# KoncovaCast.net
KiCad netlist of a schematic drawn in EAGLE
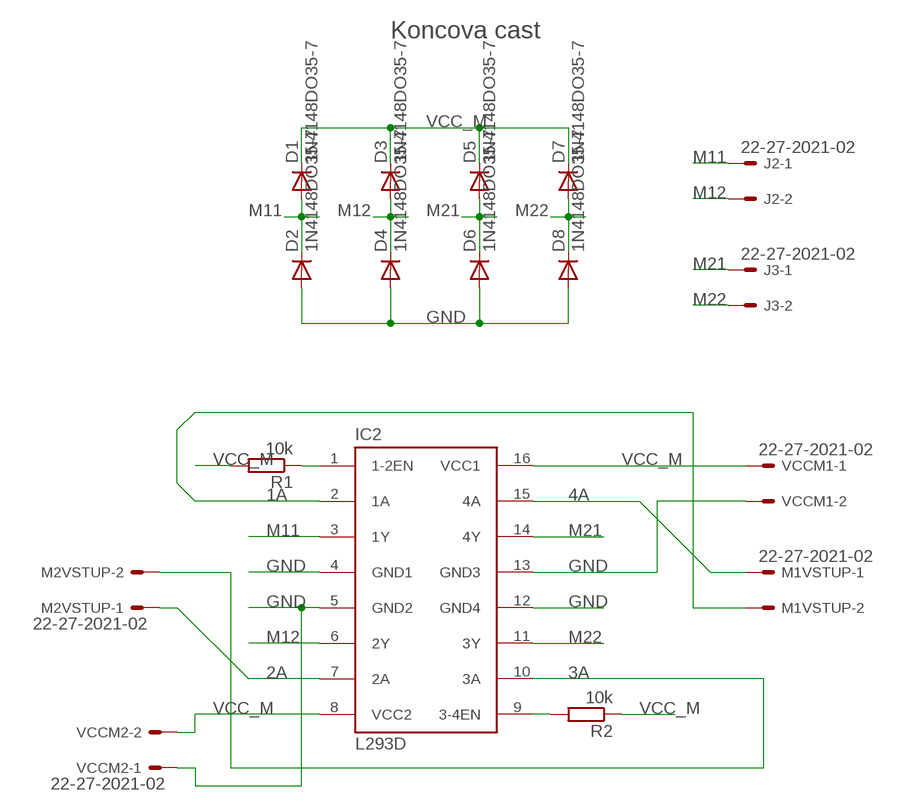
[diagram p0: schematic, sheet 1]

(export (version "E")
  (design (tool "Eeschema 10.0.6"))
  (components
    (comp (ref "D1")
      (value "1N4148DO35-7")
      (footprint "eagle-import:DO35-7")
      (libsource (lib "eagle-import") (part "1N4148DO35-7"))
    )
    (comp (ref "D2")
      (value "1N4148DO35-7")
      (footprint "eagle-import:DO35-7")
      (libsource (lib "eagle-import") (part "1N4148DO35-7"))
    )
    (comp (ref "D3")
      (value "1N4148DO35-7")
      (footprint "eagle-import:DO35-7")
      (libsource (lib "eagle-import") (part "1N4148DO35-7"))
    )
    (comp (ref "D4")
      (value "1N4148DO35-7")
      (footprint "eagle-import:DO35-7")
      (libsource (lib "eagle-import") (part "1N4148DO35-7"))
    )
    (comp (ref "D5")
      (value "1N4148DO35-7")
      (footprint "eagle-import:DO35-7")
      (libsource (lib "eagle-import") (part "1N4148DO35-7"))
    )
    (comp (ref "D6")
      (value "1N4148DO35-7")
      (footprint "eagle-import:DO35-7")
      (libsource (lib "eagle-import") (part "1N4148DO35-7"))
    )
    (comp (ref "D7")
      (value "1N4148DO35-7")
      (footprint "eagle-import:DO35-7")
      (libsource (lib "eagle-import") (part "1N4148DO35-7"))
    )
    (comp (ref "D8")
      (value "1N4148DO35-7")
      (footprint "eagle-import:DO35-7")
      (libsource (lib "eagle-import") (part "1N4148DO35-7"))
    )
    (comp (ref "IC2")
      (value "L293D")
      (footprint "eagle-import:DIL16")
      (libsource (lib "eagle-import") (part "L293D"))
    )
    (comp (ref "J2")
      (value "22-27-2021-02")
      (footprint "eagle-import:6410-02")
      (libsource (lib "eagle-import") (part "22-?-0227-2021"))
    )
    (comp (ref "J3")
      (value "22-27-2021-02")
      (footprint "eagle-import:6410-02")
      (libsource (lib "eagle-import") (part "22-?-0227-2021"))
    )
    (comp (ref "M1VSTUP")
      (value "22-27-2021-02")
      (footprint "eagle-import:6410-02")
      (libsource (lib "eagle-import") (part "22-?-0227-2021"))
    )
    (comp (ref "M2VSTUP")
      (value "22-27-2021-02")
      (footprint "eagle-import:6410-02")
      (libsource (lib "eagle-import") (part "22-?-0227-2021"))
    )
    (comp (ref "R1")
      (value "10k")
      (footprint "eagle-import:0204V")
      (libsource (lib "eagle-import") (part "R-EU_0204/2V"))
    )
    (comp (ref "R2")
      (value "10k")
      (footprint "eagle-import:0204V")
      (libsource (lib "eagle-import") (part "R-EU_0204/2V"))
    )
    (comp (ref "VCCM1")
      (value "22-27-2021-02")
      (footprint "eagle-import:6410-02")
      (libsource (lib "eagle-import") (part "22-?-0227-2021"))
    )
    (comp (ref "VCCM2")
      (value "22-27-2021-02")
      (footprint "eagle-import:6410-02")
      (libsource (lib "eagle-import") (part "22-?-0227-2021"))
    )
  )
  (nets
    (net (code "1") (name "/1A") (class "Default")
      (node (ref "IC2") (pin "2") (pinfunction "1A_2") (pintype "input"))
      (node (ref "M1VSTUP") (pin "2") (pinfunction "S_2") (pintype "passive"))
    )
    (net (code "2") (name "/2A") (class "Default")
      (node (ref "IC2") (pin "7") (pinfunction "2A_7") (pintype "input"))
      (node (ref "M2VSTUP") (pin "1") (pinfunction "S_1") (pintype "passive"))
    )
    (net (code "3") (name "/3A") (class "Default")
      (node (ref "IC2") (pin "10") (pinfunction "3A_10") (pintype "input"))
      (node (ref "M2VSTUP") (pin "2") (pinfunction "S_2") (pintype "passive"))
    )
    (net (code "4") (name "/4A") (class "Default")
      (node (ref "IC2") (pin "15") (pinfunction "4A_15") (pintype "input"))
      (node (ref "M1VSTUP") (pin "1") (pinfunction "S_1") (pintype "passive"))
    )
    (net (code "5") (name "/GND") (class "Default")
      (node (ref "D2") (pin "A") (pinfunction "A_A") (pintype "passive"))
      (node (ref "D4") (pin "A") (pinfunction "A_A") (pintype "passive"))
      (node (ref "D6") (pin "A") (pinfunction "A_A") (pintype "passive"))
      (node (ref "D8") (pin "A") (pinfunction "A_A") (pintype "passive"))
      (node (ref "IC2") (pin "12") (pinfunction "GND4_12") (pintype "power_in"))
      (node (ref "IC2") (pin "13") (pinfunction "GND3_13") (pintype "power_in"))
      (node (ref "IC2") (pin "4") (pinfunction "GND1_4") (pintype "power_in"))
      (node (ref "IC2") (pin "5") (pinfunction "GND2_5") (pintype "power_in"))
      (node (ref "VCCM1") (pin "2") (pinfunction "S_2") (pintype "passive"))
      (node (ref "VCCM2") (pin "1") (pinfunction "S_1") (pintype "passive"))
    )
    (net (code "6") (name "/M11") (class "Default")
      (node (ref "D1") (pin "A") (pinfunction "A_A") (pintype "passive"))
      (node (ref "D2") (pin "C") (pinfunction "C_C") (pintype "passive"))
      (node (ref "IC2") (pin "3") (pinfunction "1Y_3") (pintype "output"))
      (node (ref "J2") (pin "1") (pinfunction "S_1") (pintype "passive"))
    )
    (net (code "7") (name "/M12") (class "Default")
      (node (ref "D3") (pin "A") (pinfunction "A_A") (pintype "passive"))
      (node (ref "D4") (pin "C") (pinfunction "C_C") (pintype "passive"))
      (node (ref "IC2") (pin "6") (pinfunction "2Y_6") (pintype "output"))
      (node (ref "J2") (pin "2") (pinfunction "S_2") (pintype "passive"))
    )
    (net (code "8") (name "/M21") (class "Default")
      (node (ref "D5") (pin "A") (pinfunction "A_A") (pintype "passive"))
      (node (ref "D6") (pin "C") (pinfunction "C_C") (pintype "passive"))
      (node (ref "IC2") (pin "14") (pinfunction "4Y_14") (pintype "output"))
      (node (ref "J3") (pin "1") (pinfunction "S_1") (pintype "passive"))
    )
    (net (code "9") (name "/M22") (class "Default")
      (node (ref "D7") (pin "A") (pinfunction "A_A") (pintype "passive"))
      (node (ref "D8") (pin "C") (pinfunction "C_C") (pintype "passive"))
      (node (ref "IC2") (pin "11") (pinfunction "3Y_11") (pintype "output"))
      (node (ref "J3") (pin "2") (pinfunction "S_2") (pintype "passive"))
    )
    (net (code "10") (name "/VCC_M") (class "Default")
      (node (ref "D1") (pin "C") (pinfunction "C_C") (pintype "passive"))
      (node (ref "D3") (pin "C") (pinfunction "C_C") (pintype "passive"))
      (node (ref "D5") (pin "C") (pinfunction "C_C") (pintype "passive"))
      (node (ref "D7") (pin "C") (pinfunction "C_C") (pintype "passive"))
      (node (ref "IC2") (pin "16") (pinfunction "VCC1_16") (pintype "power_in"))
      (node (ref "IC2") (pin "8") (pinfunction "VCC2_8") (pintype "power_in"))
      (node (ref "R1") (pin "2") (pinfunction "2_2") (pintype "passive"))
      (node (ref "R2") (pin "1") (pinfunction "1_1") (pintype "passive"))
      (node (ref "VCCM1") (pin "1") (pinfunction "S_1") (pintype "passive"))
      (node (ref "VCCM2") (pin "2") (pinfunction "S_2") (pintype "passive"))
    )
    (net (code "11") (name "Net-(IC2-1-2EN)") (class "Default")
      (node (ref "IC2") (pin "1") (pinfunction "1-2EN_1") (pintype "input"))
      (node (ref "R1") (pin "1") (pinfunction "1_1") (pintype "passive"))
    )
    (net (code "12") (name "Net-(IC2-3-4EN)") (class "Default")
      (node (ref "IC2") (pin "9") (pinfunction "3-4EN_9") (pintype "input"))
      (node (ref "R2") (pin "2") (pinfunction "2_2") (pintype "passive"))
    )
  )
)
